# Sheet1.net
KiCad netlist of a schematic drawn in Altium Designer
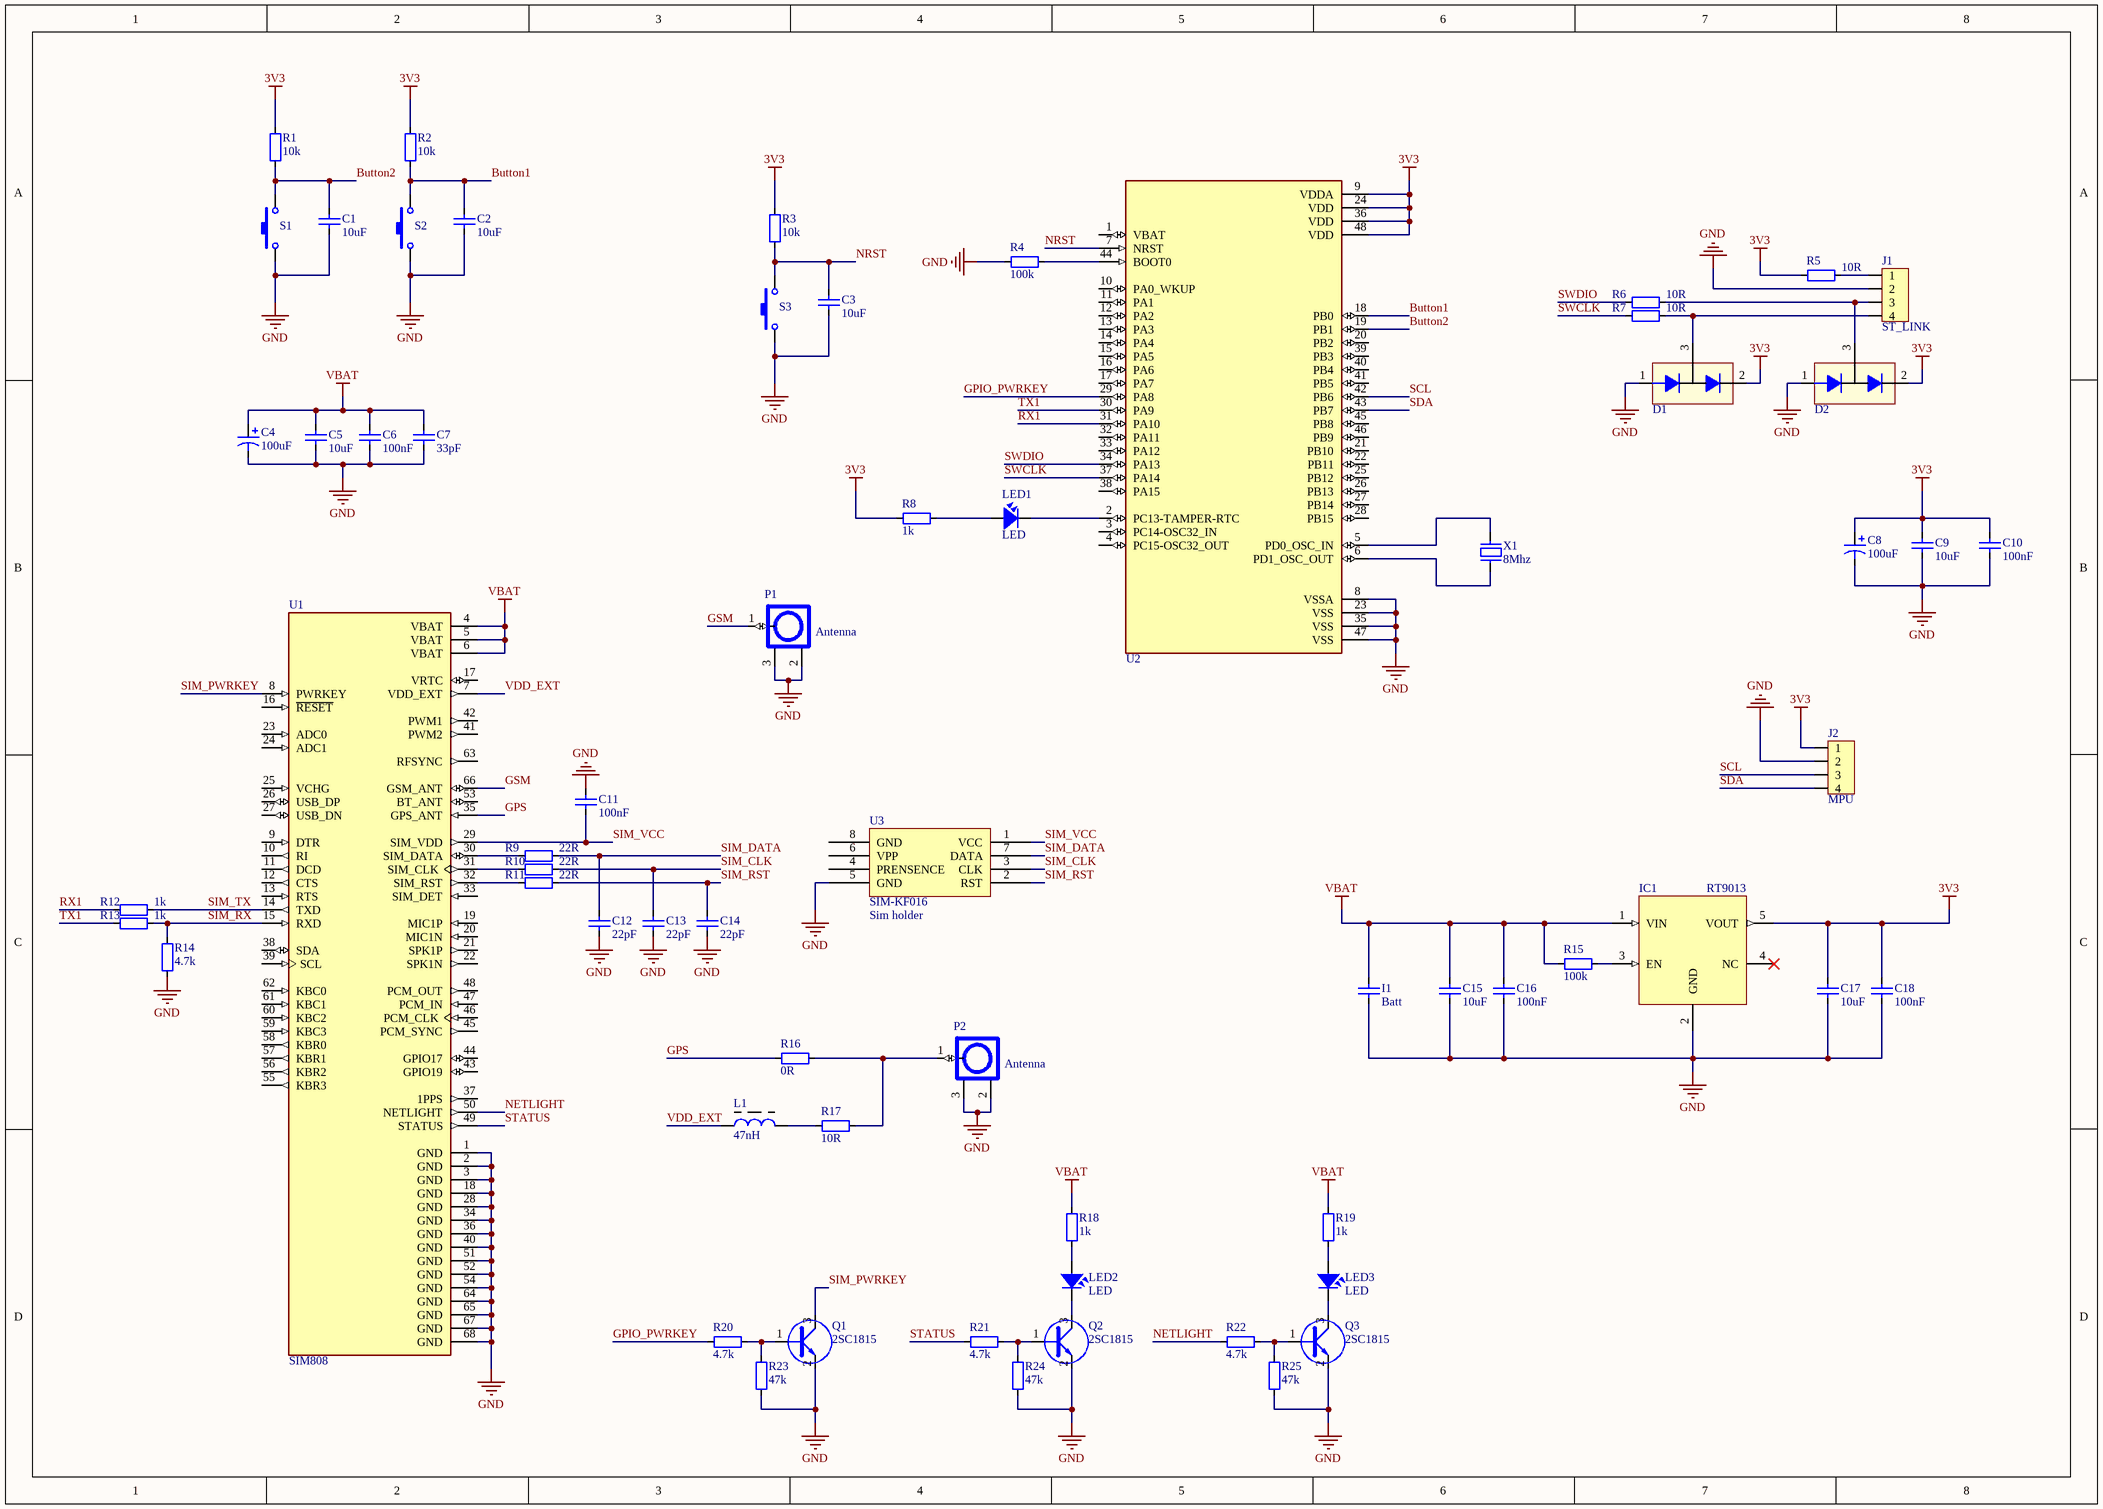
[diagram p0: Sheet1.SchDoc]

(export (version "E")
  (design (tool "Eeschema 10.0.6"))
  (components
    (comp (ref "C1")
      (value "10uF")
      (footprint "CAP_0603")
      (description "Capacitor")
      (fields (field (name "PUBLISHER") "Altium Limited"))
      (libsource (lib "My Library") (part "CapSMD"))
    )
    (comp (ref "C2")
      (value "10uF")
      (footprint "CAP_0603")
      (description "Capacitor")
      (fields (field (name "PUBLISHER") "Altium Limited"))
      (libsource (lib "My Library") (part "CapSMD"))
    )
    (comp (ref "C3")
      (value "10uF")
      (footprint "CAP_0603")
      (description "Capacitor")
      (fields (field (name "PUBLISHER") "Altium Limited"))
      (libsource (lib "My Library") (part "CapSMD"))
    )
    (comp (ref "C4")
      (value "100uF")
      (footprint "CAP_7343")
      (description "Tantalum")
      (fields (field (name "PUBLISHER") "Altium Limited"))
      (libsource (lib "My Library") (part "Cap Pol"))
    )
    (comp (ref "C5")
      (value "10uF")
      (footprint "CAP_0603")
      (description "Capacitor")
      (fields (field (name "PUBLISHER") "Altium Limited"))
      (libsource (lib "My Library") (part "CapSMD"))
    )
    (comp (ref "C6")
      (value "100nF")
      (footprint "CAP_0603")
      (description "Capacitor")
      (fields (field (name "PUBLISHER") "Altium Limited"))
      (libsource (lib "My Library") (part "CapSMD"))
    )
    (comp (ref "C7")
      (value "33pF")
      (footprint "CAP_0603")
      (description "Capacitor")
      (fields (field (name "PUBLISHER") "Altium Limited"))
      (libsource (lib "My Library") (part "CapSMD"))
    )
    (comp (ref "C8")
      (value "100uF")
      (footprint "CAP_7343")
      (description "Tantalum")
      (fields (field (name "PUBLISHER") "Altium Limited"))
      (libsource (lib "My Library") (part "Cap Pol"))
    )
    (comp (ref "C9")
      (value "10uF")
      (footprint "CAP_0603")
      (description "Capacitor")
      (fields (field (name "PUBLISHER") "Altium Limited"))
      (libsource (lib "My Library") (part "CapSMD"))
    )
    (comp (ref "C10")
      (value "100nF")
      (footprint "CAP_0603")
      (description "Capacitor")
      (fields (field (name "PUBLISHER") "Altium Limited"))
      (libsource (lib "My Library") (part "CapSMD"))
    )
    (comp (ref "C11")
      (value "100nF")
      (footprint "CAP_0603")
      (description "Capacitor")
      (fields (field (name "PUBLISHER") "Altium Limited"))
      (libsource (lib "My Library") (part "CapSMD"))
    )
    (comp (ref "C12")
      (value "22pF")
      (footprint "CAP_0603")
      (description "Capacitor")
      (fields (field (name "PUBLISHER") "Altium Limited"))
      (libsource (lib "My Library") (part "CapSMD"))
    )
    (comp (ref "C13")
      (value "22pF")
      (footprint "CAP_0603")
      (description "Capacitor")
      (fields (field (name "PUBLISHER") "Altium Limited"))
      (libsource (lib "My Library") (part "CapSMD"))
    )
    (comp (ref "C14")
      (value "22pF")
      (footprint "CAP_0603")
      (description "Capacitor")
      (fields (field (name "PUBLISHER") "Altium Limited"))
      (libsource (lib "My Library") (part "CapSMD"))
    )
    (comp (ref "C15")
      (value "10uF")
      (footprint "CAP_0603")
      (description "Capacitor")
      (fields (field (name "PUBLISHER") "Altium Limited"))
      (libsource (lib "My Library") (part "CapSMD"))
    )
    (comp (ref "C16")
      (value "100nF")
      (footprint "CAP_0603")
      (description "Capacitor")
      (fields (field (name "PUBLISHER") "Altium Limited"))
      (libsource (lib "My Library") (part "CapSMD"))
    )
    (comp (ref "C17")
      (value "10uF")
      (footprint "CAP_0603")
      (description "Capacitor")
      (fields (field (name "PUBLISHER") "Altium Limited"))
      (libsource (lib "My Library") (part "CapSMD"))
    )
    (comp (ref "C18")
      (value "100nF")
      (footprint "CAP_0603")
      (description "Capacitor")
      (fields (field (name "PUBLISHER") "Altium Limited"))
      (libsource (lib "My Library") (part "CapSMD"))
    )
    (comp (ref "D1")
      (value "DIODE-BAV99")
      (footprint "SOT23")
      (description "ZENER, SOT23,")
      (fields
        (field (name "MANUFACTURER") "ON Semiconductor / Fairchild")
        (field (name "MANUFACTURER PART NUMBER") "BAV99")
        (field (name ".CREATOR") "LeKhaLinh")
        (field (name ".CHECKPCB") "LeKhaLinh")
        (field (name ".CHECKSCH") "LeKhaLinh")
      )
      (libsource (lib "GPS_Traking_V1_1") (part "DIODE-BAV99"))
    )
    (comp (ref "D2")
      (value "DIODE-BAV99")
      (footprint "SOT23")
      (description "ZENER, SOT23,")
      (fields
        (field (name "MANUFACTURER") "ON Semiconductor / Fairchild")
        (field (name "MANUFACTURER PART NUMBER") "BAV99")
        (field (name ".CREATOR") "LeKhaLinh")
        (field (name ".CHECKPCB") "LeKhaLinh")
        (field (name ".CHECKSCH") "LeKhaLinh")
      )
      (libsource (lib "GPS_Traking_V1_1") (part "DIODE-BAV99"))
    )
    (comp (ref "I1")
      (value "Batt")
      (footprint "CAP_3216")
      (description "Pad")
      (fields (field (name "PUBLISHER") "Altium Limited"))
      (libsource (lib "My Library") (part "CapSMD"))
    )
    (comp (ref "IC1")
      (value "RT9013")
      (footprint "SOT23-5")
      (description "RT9013-33GB IC REG LINEAR 3.3V 500mA SOT23-5")
      (libsource (lib "My Library") (part "RT9013"))
    )
    (comp (ref "J1")
      (value "ST_LINK")
      (footprint "JP4-D1T")
      (description "Header IDC, 4 x 1 Pin Vertical 2.54mm Pitch (Non-Boxed, Male)")
      (fields
        (field (name "MANUFACTURER") "Würth Elektronik eiSos GmbH")
        (field (name "PARTNO") "613002143121")
        (field (name "CREATED BY") "Karrer Zheng")
      )
      (libsource (lib "My Library") (part "Header4"))
    )
    (comp (ref "J2")
      (value "MPU")
      (footprint "JP4-D1T")
      (description "Header IDC, 4 x 1 Pin Vertical 2.54mm Pitch (Non-Boxed, Male)")
      (fields
        (field (name "MANUFACTURER") "Würth Elektronik eiSos GmbH")
        (field (name "PARTNO") "613002143121")
        (field (name "CREATED BY") "Karrer Zheng")
      )
      (libsource (lib "My Library") (part "Header4"))
    )
    (comp (ref "L1")
      (value "47nH")
      (footprint "L-0805")
      (description "Inductor")
      (libsource (lib "My Library") (part "Inductor Ferit"))
    )
    (comp (ref "LED1")
      (value "LED")
      (footprint "LED-0805-Orange")
      (description "LED Single colour Green and Red")
      (libsource (lib "My Library") (part "LED"))
    )
    (comp (ref "LED2")
      (value "LED")
      (footprint "LED-0805-Yellow")
      (description "LED Single colour Green and Red")
      (libsource (lib "My Library") (part "LED"))
    )
    (comp (ref "LED3")
      (value "LED")
      (footprint "LED-0805-Red")
      (description "LED Single colour Green and Red")
      (libsource (lib "My Library") (part "LED"))
    )
    (comp (ref "P1")
      (value "Antenna")
      (footprint "IPXS")
      (description "Antenna GSM GPS")
      (libsource (lib "My Library") (part "IPXSx66"))
    )
    (comp (ref "P2")
      (value "Antenna")
      (footprint "IPXS")
      (description "Antenna GSM GPS")
      (libsource (lib "My Library") (part "IPXSx66"))
    )
    (comp (ref "Q1")
      (value "2SC1815")
      (footprint "SOT23D")
      (description "NPN 600mW, ECB")
      (libsource (lib "My Library") (part "2SC1815"))
    )
    (comp (ref "Q2")
      (value "2SC1815")
      (footprint "SOT23D")
      (description "NPN 600mW, ECB")
      (libsource (lib "My Library") (part "2SC1815"))
    )
    (comp (ref "Q3")
      (value "2SC1815")
      (footprint "SOT23D")
      (description "NPN 600mW, ECB")
      (libsource (lib "My Library") (part "2SC1815"))
    )
    (comp (ref "R1")
      (value "10k")
      (footprint "RES-SMD-0603")
      (description "Resistor")
      (fields
        (field (name "MANUFACTURER") "Generic Components")
        (field (name "PUBLISHER") "Altium Hobart Technology Centre")
      )
      (libsource (lib "My Library") (part "Resistor - SMD"))
    )
    (comp (ref "R2")
      (value "10k")
      (footprint "RES-SMD-0603")
      (description "Resistor")
      (fields
        (field (name "MANUFACTURER") "Generic Components")
        (field (name "PUBLISHER") "Altium Hobart Technology Centre")
      )
      (libsource (lib "My Library") (part "Resistor - SMD"))
    )
    (comp (ref "R3")
      (value "10k")
      (footprint "RES-SMD-0603")
      (description "Resistor")
      (fields
        (field (name "MANUFACTURER") "Generic Components")
        (field (name "PUBLISHER") "Altium Hobart Technology Centre")
      )
      (libsource (lib "My Library") (part "Resistor - SMD"))
    )
    (comp (ref "R4")
      (value "100k")
      (footprint "RES-SMD-0603")
      (description "Resistor")
      (fields
        (field (name "MANUFACTURER") "Generic Components")
        (field (name "PUBLISHER") "Altium Hobart Technology Centre")
      )
      (libsource (lib "My Library") (part "Resistor - SMD"))
    )
    (comp (ref "R5")
      (value "10R")
      (footprint "RES-SMD-0603")
      (description "Resistor")
      (fields
        (field (name "MANUFACTURER") "Generic Components")
        (field (name "PUBLISHER") "Altium Hobart Technology Centre")
      )
      (libsource (lib "My Library") (part "Resistor - SMD"))
    )
    (comp (ref "R6")
      (value "10R")
      (footprint "RES-SMD-0603")
      (description "Resistor")
      (fields
        (field (name "MANUFACTURER") "Generic Components")
        (field (name "PUBLISHER") "Altium Hobart Technology Centre")
      )
      (libsource (lib "My Library") (part "Resistor - SMD"))
    )
    (comp (ref "R7")
      (value "10R")
      (footprint "RES-SMD-0603")
      (description "Resistor")
      (fields
        (field (name "MANUFACTURER") "Generic Components")
        (field (name "PUBLISHER") "Altium Hobart Technology Centre")
      )
      (libsource (lib "My Library") (part "Resistor - SMD"))
    )
    (comp (ref "R8")
      (value "1k")
      (footprint "RES-SMD-0603")
      (description "Resistor")
      (fields
        (field (name "MANUFACTURER") "Generic Components")
        (field (name "PUBLISHER") "Altium Hobart Technology Centre")
      )
      (libsource (lib "My Library") (part "Resistor - SMD"))
    )
    (comp (ref "R9")
      (value "22R")
      (footprint "RES-SMD-0603")
      (description "Resistor")
      (fields
        (field (name "MANUFACTURER") "Generic Components")
        (field (name "PUBLISHER") "Altium Hobart Technology Centre")
      )
      (libsource (lib "My Library") (part "Resistor - SMD"))
    )
    (comp (ref "R10")
      (value "22R")
      (footprint "RES-SMD-0603")
      (description "Resistor")
      (fields
        (field (name "MANUFACTURER") "Generic Components")
        (field (name "PUBLISHER") "Altium Hobart Technology Centre")
      )
      (libsource (lib "My Library") (part "Resistor - SMD"))
    )
    (comp (ref "R11")
      (value "22R")
      (footprint "RES-SMD-0603")
      (description "Resistor")
      (fields
        (field (name "MANUFACTURER") "Generic Components")
        (field (name "PUBLISHER") "Altium Hobart Technology Centre")
      )
      (libsource (lib "My Library") (part "Resistor - SMD"))
    )
    (comp (ref "R12")
      (value "1k")
      (footprint "RES-SMD-0603")
      (description "Resistor")
      (fields
        (field (name "MANUFACTURER") "Generic Components")
        (field (name "PUBLISHER") "Altium Hobart Technology Centre")
      )
      (libsource (lib "My Library") (part "Resistor - SMD"))
    )
    (comp (ref "R13")
      (value "1k")
      (footprint "RES-SMD-0603")
      (description "Resistor")
      (fields
        (field (name "MANUFACTURER") "Generic Components")
        (field (name "PUBLISHER") "Altium Hobart Technology Centre")
      )
      (libsource (lib "My Library") (part "Resistor - SMD"))
    )
    (comp (ref "R14")
      (value "4.7k")
      (footprint "RES-SMD-0603")
      (description "Resistor")
      (fields
        (field (name "MANUFACTURER") "Generic Components")
        (field (name "PUBLISHER") "Altium Hobart Technology Centre")
      )
      (libsource (lib "My Library") (part "Resistor - SMD"))
    )
    (comp (ref "R15")
      (value "100k")
      (footprint "RES-SMD-0603")
      (description "Resistor")
      (fields
        (field (name "MANUFACTURER") "Generic Components")
        (field (name "PUBLISHER") "Altium Hobart Technology Centre")
      )
      (libsource (lib "My Library") (part "Resistor - SMD"))
    )
    (comp (ref "R16")
      (value "0R")
      (footprint "RES-SMD-0805")
      (description "Resistor")
      (fields
        (field (name "MANUFACTURER") "Generic Components")
        (field (name "PUBLISHER") "Altium Hobart Technology Centre")
      )
      (libsource (lib "My Library") (part "Resistor - SMD"))
    )
    (comp (ref "R17")
      (value "10R")
      (footprint "RES-SMD-0805")
      (description "Resistor")
      (fields
        (field (name "MANUFACTURER") "Generic Components")
        (field (name "PUBLISHER") "Altium Hobart Technology Centre")
      )
      (libsource (lib "My Library") (part "Resistor - SMD"))
    )
    (comp (ref "R18")
      (value "1k")
      (footprint "RES-SMD-0603")
      (description "Resistor")
      (fields
        (field (name "MANUFACTURER") "Generic Components")
        (field (name "PUBLISHER") "Altium Hobart Technology Centre")
      )
      (libsource (lib "My Library") (part "Resistor - SMD"))
    )
    (comp (ref "R19")
      (value "1k")
      (footprint "RES-SMD-0603")
      (description "Resistor")
      (fields
        (field (name "MANUFACTURER") "Generic Components")
        (field (name "PUBLISHER") "Altium Hobart Technology Centre")
      )
      (libsource (lib "My Library") (part "Resistor - SMD"))
    )
    (comp (ref "R20")
      (value "4.7k")
      (footprint "RES-SMD-0603")
      (description "Resistor")
      (fields
        (field (name "MANUFACTURER") "Generic Components")
        (field (name "PUBLISHER") "Altium Hobart Technology Centre")
      )
      (libsource (lib "My Library") (part "Resistor - SMD"))
    )
    (comp (ref "R21")
      (value "4.7k")
      (footprint "RES-SMD-0603")
      (description "Resistor")
      (fields
        (field (name "MANUFACTURER") "Generic Components")
        (field (name "PUBLISHER") "Altium Hobart Technology Centre")
      )
      (libsource (lib "My Library") (part "Resistor - SMD"))
    )
    (comp (ref "R22")
      (value "4.7k")
      (footprint "RES-SMD-0603")
      (description "Resistor")
      (fields
        (field (name "MANUFACTURER") "Generic Components")
        (field (name "PUBLISHER") "Altium Hobart Technology Centre")
      )
      (libsource (lib "My Library") (part "Resistor - SMD"))
    )
    (comp (ref "R23")
      (value "47k")
      (footprint "RES-SMD-0603")
      (description "Resistor")
      (fields
        (field (name "MANUFACTURER") "Generic Components")
        (field (name "PUBLISHER") "Altium Hobart Technology Centre")
      )
      (libsource (lib "My Library") (part "Resistor - SMD"))
    )
    (comp (ref "R24")
      (value "47k")
      (footprint "RES-SMD-0603")
      (description "Resistor")
      (fields
        (field (name "MANUFACTURER") "Generic Components")
        (field (name "PUBLISHER") "Altium Hobart Technology Centre")
      )
      (libsource (lib "My Library") (part "Resistor - SMD"))
    )
    (comp (ref "R25")
      (value "47k")
      (footprint "RES-SMD-0603")
      (description "Resistor")
      (fields
        (field (name "MANUFACTURER") "Generic Components")
        (field (name "PUBLISHER") "Altium Hobart Technology Centre")
      )
      (libsource (lib "My Library") (part "Resistor - SMD"))
    )
    (comp (ref "S1")
      (value "SW-SMD")
      (footprint "SW 3x2x4")
      (description "Switch")
      (fields (field (name "PUBLISHER") "Altium Limited"))
      (libsource (lib "My Library") (part "SW-SMD"))
    )
    (comp (ref "S2")
      (value "SW-SMD")
      (footprint "SW 3x2x4")
      (description "Switch")
      (fields (field (name "PUBLISHER") "Altium Limited"))
      (libsource (lib "My Library") (part "SW-SMD"))
    )
    (comp (ref "S3")
      (value "SW-SMD")
      (footprint "SW 3x2x4")
      (description "Switch")
      (fields (field (name "PUBLISHER") "Altium Limited"))
      (libsource (lib "My Library") (part "SW-SMD"))
    )
    (comp (ref "U1")
      (value "SIM808")
      (footprint "XCVR_SIM808")
      (description "SIM808 GPS, GPRS/GSM RF Arduino Platform Evaluation Expansion Board")
      (fields (field (name "MF") "Adafruit Industries"))
      (libsource (lib "My Library") (part "SIM808"))
    )
    (comp (ref "U2")
      (value "STM32")
      (footprint "LQFP 48")
      (description "STM32 ARM-based 32-bit MCU with 64 Kbytes Flash, 64-pin LQFP, Industrial Temperature")
      (libsource (lib "My Library") (part "STM32F103C8T6"))
    )
    (comp (ref "U3")
      (value "SIM-KF016")
      (footprint "Sim Socket")
      (description "SIM Card Holder KF-016")
      (fields (field (name "ALTIUM_VALUE") "Sim holder"))
      (libsource (lib "My Library") (part "Sim holder"))
    )
    (comp (ref "X1")
      (value "8Mhz")
      (footprint "XTAL 5032 SMD")
      (description "Crystal For all Crystal 2pin.")
      (libsource (lib "My Library") (part "XT2"))
    )
  )
  (nets
    (net (code "1") (name "/Button1") (class "Default")
      (node (ref "C2") (pin "2") (pinfunction "2_2") (pintype "passive"))
      (node (ref "R2") (pin "1") (pinfunction "1_1") (pintype "passive"))
      (node (ref "S2") (pin "2") (pinfunction "2_2") (pintype "passive"))
      (node (ref "U2") (pin "18") (pinfunction "PB0_18") (pintype "bidirectional"))
    )
    (net (code "2") (name "/Button2") (class "Default")
      (node (ref "C1") (pin "2") (pinfunction "2_2") (pintype "passive"))
      (node (ref "R1") (pin "1") (pinfunction "1_1") (pintype "passive"))
      (node (ref "S1") (pin "2") (pinfunction "2_2") (pintype "passive"))
      (node (ref "U2") (pin "19") (pinfunction "PB1_19") (pintype "bidirectional"))
    )
    (net (code "3") (name "/GPIO_PWRKEY") (class "Default")
      (node (ref "R20") (pin "1") (pinfunction "1_1") (pintype "passive"))
      (node (ref "U2") (pin "29") (pinfunction "PA8_29") (pintype "bidirectional"))
    )
    (net (code "4") (name "/GPS") (class "Default")
      (node (ref "R16") (pin "1") (pinfunction "1_1") (pintype "passive"))
      (node (ref "U1") (pin "35") (pinfunction "GPS_ANT_35") (pintype "input"))
    )
    (net (code "5") (name "/GSM") (class "Default")
      (node (ref "P1") (pin "1") (pintype "bidirectional"))
      (node (ref "U1") (pin "66") (pinfunction "GSM_ANT_66") (pintype "bidirectional"))
    )
    (net (code "6") (name "/NETLIGHT") (class "Default")
      (node (ref "R22") (pin "1") (pinfunction "1_1") (pintype "passive"))
      (node (ref "U1") (pin "50") (pinfunction "NETLIGHT_50") (pintype "output"))
    )
    (net (code "7") (name "/NRST") (class "Default")
      (node (ref "C3") (pin "2") (pinfunction "2_2") (pintype "passive"))
      (node (ref "R3") (pin "1") (pinfunction "1_1") (pintype "passive"))
      (node (ref "S3") (pin "2") (pinfunction "2_2") (pintype "passive"))
      (node (ref "U2") (pin "7") (pinfunction "NRST_7") (pintype "input"))
    )
    (net (code "8") (name "/RX1") (class "Default")
      (node (ref "R12") (pin "2") (pinfunction "2_2") (pintype "passive"))
      (node (ref "U2") (pin "31") (pinfunction "PA10_31") (pintype "bidirectional"))
    )
    (net (code "9") (name "/SCL") (class "Default")
      (node (ref "J2") (pin "3") (pinfunction "3_3") (pintype "passive"))
      (node (ref "U2") (pin "42") (pinfunction "PB6_42") (pintype "bidirectional"))
    )
    (net (code "10") (name "/SDA") (class "Default")
      (node (ref "J2") (pin "4") (pinfunction "4_4") (pintype "passive"))
      (node (ref "U2") (pin "43") (pinfunction "PB7_43") (pintype "bidirectional"))
    )
    (net (code "11") (name "/SIM_CLK") (class "Default")
      (node (ref "C13") (pin "1") (pinfunction "1_1") (pintype "passive"))
      (node (ref "R10") (pin "1") (pinfunction "1_1") (pintype "passive"))
      (node (ref "U3") (pin "3") (pinfunction "CLK_3") (pintype "passive"))
    )
    (net (code "12") (name "/SIM_DATA") (class "Default")
      (node (ref "C12") (pin "1") (pinfunction "1_1") (pintype "passive"))
      (node (ref "R9") (pin "1") (pinfunction "1_1") (pintype "passive"))
      (node (ref "U3") (pin "7") (pinfunction "DATA_7") (pintype "passive"))
    )
    (net (code "13") (name "/SIM_PWRKEY") (class "Default")
      (node (ref "Q1") (pin "3") (pinfunction "C_3") (pintype "passive"))
      (node (ref "U1") (pin "8") (pinfunction "PWRKEY_8") (pintype "input"))
    )
    (net (code "14") (name "/SIM_RST") (class "Default")
      (node (ref "C14") (pin "1") (pinfunction "1_1") (pintype "passive"))
      (node (ref "R11") (pin "1") (pinfunction "1_1") (pintype "passive"))
      (node (ref "U3") (pin "2") (pinfunction "RST_2") (pintype "passive"))
    )
    (net (code "15") (name "/SIM_RX") (class "Default")
      (node (ref "R13") (pin "1") (pinfunction "1_1") (pintype "passive"))
      (node (ref "R14") (pin "1") (pinfunction "1_1") (pintype "passive"))
      (node (ref "U1") (pin "15") (pinfunction "RXD_15") (pintype "input"))
    )
    (net (code "16") (name "/SIM_TX") (class "Default")
      (node (ref "R12") (pin "1") (pinfunction "1_1") (pintype "passive"))
      (node (ref "U1") (pin "14") (pinfunction "TXD_14") (pintype "output"))
    )
    (net (code "17") (name "/SIM_VCC") (class "Default")
      (node (ref "C11") (pin "2") (pinfunction "2_2") (pintype "passive"))
      (node (ref "U1") (pin "29") (pinfunction "SIM_VDD_29") (pintype "output"))
      (node (ref "U3") (pin "1") (pinfunction "VCC_1") (pintype "passive"))
    )
    (net (code "18") (name "/STATUS") (class "Default")
      (node (ref "R21") (pin "1") (pinfunction "1_1") (pintype "passive"))
      (node (ref "U1") (pin "49") (pinfunction "STATUS_49") (pintype "output"))
    )
    (net (code "19") (name "/SWCLK") (class "Default")
      (node (ref "R7") (pin "1") (pinfunction "1_1") (pintype "passive"))
      (node (ref "U2") (pin "37") (pinfunction "PA14_37") (pintype "bidirectional"))
    )
    (net (code "20") (name "/SWDIO") (class "Default")
      (node (ref "R6") (pin "1") (pinfunction "1_1") (pintype "passive"))
      (node (ref "U2") (pin "34") (pinfunction "PA13_34") (pintype "bidirectional"))
    )
    (net (code "21") (name "/TX1") (class "Default")
      (node (ref "R13") (pin "2") (pinfunction "2_2") (pintype "passive"))
      (node (ref "U2") (pin "30") (pinfunction "PA9_30") (pintype "bidirectional"))
    )
    (net (code "22") (name "/VDD_EXT") (class "Default")
      (node (ref "L1") (pin "1") (pinfunction "1_1") (pintype "passive"))
      (node (ref "U1") (pin "7") (pinfunction "VDD_EXT_7") (pintype "output"))
    )
    (net (code "23") (name "3V3") (class "Default")
      (node (ref "C10") (pin "2") (pinfunction "2_2") (pintype "passive"))
      (node (ref "C17") (pin "2") (pinfunction "2_2") (pintype "passive"))
      (node (ref "C18") (pin "2") (pinfunction "2_2") (pintype "passive"))
      (node (ref "C8") (pin "1") (pinfunction "1_1") (pintype "passive"))
      (node (ref "C9") (pin "2") (pinfunction "2_2") (pintype "passive"))
      (node (ref "D1") (pin "2") (pinfunction "2_2") (pintype "passive"))
      (node (ref "D2") (pin "2") (pinfunction "2_2") (pintype "passive"))
      (node (ref "IC1") (pin "5") (pinfunction "VOUT_5") (pintype "output"))
      (node (ref "J2") (pin "1") (pinfunction "1_1") (pintype "passive"))
      (node (ref "R1") (pin "2") (pinfunction "2_2") (pintype "passive"))
      (node (ref "R2") (pin "2") (pinfunction "2_2") (pintype "passive"))
      (node (ref "R3") (pin "2") (pinfunction "2_2") (pintype "passive"))
      (node (ref "R5") (pin "1") (pinfunction "1_1") (pintype "passive"))
      (node (ref "R8") (pin "1") (pinfunction "1_1") (pintype "passive"))
      (node (ref "U2") (pin "24") (pinfunction "VDD_24") (pintype "power_in"))
      (node (ref "U2") (pin "36") (pinfunction "VDD_36") (pintype "power_in"))
      (node (ref "U2") (pin "48") (pinfunction "VDD_48") (pintype "power_in"))
      (node (ref "U2") (pin "9") (pinfunction "VDDA_9") (pintype "power_in"))
    )
    (net (code "24") (name "GND") (class "Default")
      (node (ref "C1") (pin "1") (pinfunction "1_1") (pintype "passive"))
      (node (ref "C10") (pin "1") (pinfunction "1_1") (pintype "passive"))
      (node (ref "C11") (pin "1") (pinfunction "1_1") (pintype "passive"))
      (node (ref "C12") (pin "2") (pinfunction "2_2") (pintype "passive"))
      (node (ref "C13") (pin "2") (pinfunction "2_2") (pintype "passive"))
      (node (ref "C14") (pin "2") (pinfunction "2_2") (pintype "passive"))
      (node (ref "C15") (pin "1") (pinfunction "1_1") (pintype "passive"))
      (node (ref "C16") (pin "1") (pinfunction "1_1") (pintype "passive"))
      (node (ref "C17") (pin "1") (pinfunction "1_1") (pintype "passive"))
      (node (ref "C18") (pin "1") (pinfunction "1_1") (pintype "passive"))
      (node (ref "C2") (pin "1") (pinfunction "1_1") (pintype "passive"))
      (node (ref "C3") (pin "1") (pinfunction "1_1") (pintype "passive"))
      (node (ref "C4") (pin "2") (pinfunction "2_2") (pintype "passive"))
      (node (ref "C5") (pin "1") (pinfunction "1_1") (pintype "passive"))
      (node (ref "C6") (pin "1") (pinfunction "1_1") (pintype "passive"))
      (node (ref "C7") (pin "1") (pinfunction "1_1") (pintype "passive"))
      (node (ref "C8") (pin "2") (pinfunction "2_2") (pintype "passive"))
      (node (ref "C9") (pin "1") (pinfunction "1_1") (pintype "passive"))
      (node (ref "D1") (pin "1") (pinfunction "1_1") (pintype "passive"))
      (node (ref "D2") (pin "1") (pinfunction "1_1") (pintype "passive"))
      (node (ref "I1") (pin "1") (pinfunction "1_1") (pintype "passive"))
      (node (ref "IC1") (pin "2") (pinfunction "GND_2") (pintype "passive"))
      (node (ref "J1") (pin "2") (pinfunction "2_2") (pintype "passive"))
      (node (ref "J2") (pin "2") (pinfunction "2_2") (pintype "passive"))
      (node (ref "P1") (pin "2") (pintype "passive"))
      (node (ref "P1") (pin "3") (pintype "passive"))
      (node (ref "P2") (pin "2") (pintype "passive"))
      (node (ref "P2") (pin "3") (pintype "passive"))
      (node (ref "Q1") (pin "2") (pinfunction "E_2") (pintype "passive"))
      (node (ref "Q2") (pin "2") (pinfunction "E_2") (pintype "passive"))
      (node (ref "Q3") (pin "2") (pinfunction "E_2") (pintype "passive"))
      (node (ref "R14") (pin "2") (pinfunction "2_2") (pintype "passive"))
      (node (ref "R23") (pin "1") (pinfunction "1_1") (pintype "passive"))
      (node (ref "R24") (pin "1") (pinfunction "1_1") (pintype "passive"))
      (node (ref "R25") (pin "1") (pinfunction "1_1") (pintype "passive"))
      (node (ref "R4") (pin "2") (pinfunction "2_2") (pintype "passive"))
      (node (ref "S1") (pin "1") (pinfunction "1_1") (pintype "passive"))
      (node (ref "S2") (pin "1") (pinfunction "1_1") (pintype "passive"))
      (node (ref "S3") (pin "1") (pinfunction "1_1") (pintype "passive"))
      (node (ref "U1") (pin "1") (pinfunction "GND_1") (pintype "power_in"))
      (node (ref "U1") (pin "18") (pinfunction "GND_18") (pintype "power_in"))
      (node (ref "U1") (pin "2") (pinfunction "GND_2") (pintype "power_in"))
      (node (ref "U1") (pin "28") (pinfunction "GND_28") (pintype "power_in"))
      (node (ref "U1") (pin "3") (pinfunction "GND_3") (pintype "power_in"))
      (node (ref "U1") (pin "34") (pinfunction "GND_34") (pintype "power_in"))
      (node (ref "U1") (pin "36") (pinfunction "GND_36") (pintype "power_in"))
      (node (ref "U1") (pin "40") (pinfunction "GND_40") (pintype "power_in"))
      (node (ref "U1") (pin "51") (pinfunction "GND_51") (pintype "power_in"))
      (node (ref "U1") (pin "52") (pinfunction "GND_52") (pintype "power_in"))
      (node (ref "U1") (pin "54") (pinfunction "GND_54") (pintype "power_in"))
      (node (ref "U1") (pin "64") (pinfunction "GND_64") (pintype "power_in"))
      (node (ref "U1") (pin "65") (pinfunction "GND_65") (pintype "power_in"))
      (node (ref "U1") (pin "67") (pinfunction "GND_67") (pintype "power_in"))
      (node (ref "U1") (pin "68") (pinfunction "GND_68") (pintype "power_in"))
      (node (ref "U2") (pin "23") (pinfunction "VSS_23") (pintype "power_in"))
      (node (ref "U2") (pin "35") (pinfunction "VSS_35") (pintype "power_in"))
      (node (ref "U2") (pin "47") (pinfunction "VSS_47") (pintype "power_in"))
      (node (ref "U2") (pin "8") (pinfunction "VSSA_8") (pintype "power_in"))
      (node (ref "U3") (pin "5") (pinfunction "GND_5") (pintype "passive"))
    )
    (net (code "25") (name "Net-(D1-Pad3)") (class "Default")
      (node (ref "D1") (pin "3") (pinfunction "3_3") (pintype "passive"))
      (node (ref "J1") (pin "4") (pinfunction "4_4") (pintype "passive"))
      (node (ref "R7") (pin "2") (pinfunction "2_2") (pintype "passive"))
    )
    (net (code "26") (name "Net-(D2-Pad3)") (class "Default")
      (node (ref "D2") (pin "3") (pinfunction "3_3") (pintype "passive"))
      (node (ref "J1") (pin "3") (pinfunction "3_3") (pintype "passive"))
      (node (ref "R6") (pin "2") (pinfunction "2_2") (pintype "passive"))
    )
    (net (code "27") (name "Net-(IC1-EN)") (class "Default")
      (node (ref "IC1") (pin "3") (pinfunction "EN_3") (pintype "input"))
      (node (ref "R15") (pin "1") (pinfunction "1_1") (pintype "passive"))
    )
    (net (code "28") (name "Net-(J1-Pad1)") (class "Default")
      (node (ref "J1") (pin "1") (pinfunction "1_1") (pintype "passive"))
      (node (ref "R5") (pin "2") (pinfunction "2_2") (pintype "passive"))
    )
    (net (code "29") (name "Net-(L1-Pad2)") (class "Default")
      (node (ref "L1") (pin "2") (pinfunction "2_2") (pintype "passive"))
      (node (ref "R17") (pin "2") (pinfunction "2_2") (pintype "passive"))
    )
    (net (code "30") (name "Net-(LED1-Pad1)") (class "Default")
      (node (ref "LED1") (pin "1") (pinfunction "1_1") (pintype "passive"))
      (node (ref "R8") (pin "2") (pinfunction "2_2") (pintype "passive"))
    )
    (net (code "31") (name "Net-(LED2-Pad1)") (class "Default")
      (node (ref "LED2") (pin "1") (pinfunction "1_1") (pintype "passive"))
      (node (ref "R18") (pin "1") (pinfunction "1_1") (pintype "passive"))
    )
    (net (code "32") (name "Net-(LED3-Pad1)") (class "Default")
      (node (ref "LED3") (pin "1") (pinfunction "1_1") (pintype "passive"))
      (node (ref "R19") (pin "1") (pinfunction "1_1") (pintype "passive"))
    )
    (net (code "33") (name "Net-(P2-Pad1)") (class "Default")
      (node (ref "P2") (pin "1") (pintype "bidirectional"))
      (node (ref "R16") (pin "2") (pinfunction "2_2") (pintype "passive"))
      (node (ref "R17") (pin "1") (pinfunction "1_1") (pintype "passive"))
    )
    (net (code "34") (name "Net-(Q1-B)") (class "Default")
      (node (ref "Q1") (pin "1") (pinfunction "B_1") (pintype "passive"))
      (node (ref "R20") (pin "2") (pinfunction "2_2") (pintype "passive"))
      (node (ref "R23") (pin "2") (pinfunction "2_2") (pintype "passive"))
    )
    (net (code "35") (name "Net-(Q2-B)") (class "Default")
      (node (ref "Q2") (pin "1") (pinfunction "B_1") (pintype "passive"))
      (node (ref "R21") (pin "2") (pinfunction "2_2") (pintype "passive"))
      (node (ref "R24") (pin "2") (pinfunction "2_2") (pintype "passive"))
    )
    (net (code "36") (name "Net-(Q2-C)") (class "Default")
      (node (ref "LED2") (pin "2") (pinfunction "2_2") (pintype "passive"))
      (node (ref "Q2") (pin "3") (pinfunction "C_3") (pintype "passive"))
    )
    (net (code "37") (name "Net-(Q3-B)") (class "Default")
      (node (ref "Q3") (pin "1") (pinfunction "B_1") (pintype "passive"))
      (node (ref "R22") (pin "2") (pinfunction "2_2") (pintype "passive"))
      (node (ref "R25") (pin "2") (pinfunction "2_2") (pintype "passive"))
    )
    (net (code "38") (name "Net-(Q3-C)") (class "Default")
      (node (ref "LED3") (pin "2") (pinfunction "2_2") (pintype "passive"))
      (node (ref "Q3") (pin "3") (pinfunction "C_3") (pintype "passive"))
    )
    (net (code "39") (name "Net-(U1-SIM_CLK)") (class "Default")
      (node (ref "R10") (pin "2") (pinfunction "2_2") (pintype "passive"))
      (node (ref "U1") (pin "31") (pinfunction "SIM_CLK_31") (pintype "output"))
    )
    (net (code "40") (name "Net-(U1-SIM_DATA)") (class "Default")
      (node (ref "R9") (pin "2") (pinfunction "2_2") (pintype "passive"))
      (node (ref "U1") (pin "30") (pinfunction "SIM_DATA_30") (pintype "bidirectional"))
    )
    (net (code "41") (name "Net-(U1-SIM_RST)") (class "Default")
      (node (ref "R11") (pin "2") (pinfunction "2_2") (pintype "passive"))
      (node (ref "U1") (pin "32") (pinfunction "SIM_RST_32") (pintype "output"))
    )
    (net (code "42") (name "Net-(U2-BOOT0)") (class "Default")
      (node (ref "R4") (pin "1") (pinfunction "1_1") (pintype "passive"))
      (node (ref "U2") (pin "44") (pinfunction "BOOT0_44") (pintype "input"))
    )
    (net (code "43") (name "Net-(U2-PC13-TAMPER-RTC)") (class "Default")
      (node (ref "LED1") (pin "2") (pinfunction "2_2") (pintype "passive"))
      (node (ref "U2") (pin "2") (pinfunction "PC13-TAMPER-RTC_2") (pintype "bidirectional"))
    )
    (net (code "44") (name "Net-(U2-PD0_OSC_IN)") (class "Default")
      (node (ref "U2") (pin "5") (pinfunction "PD0_OSC_IN_5") (pintype "bidirectional"))
      (node (ref "X1") (pin "2") (pinfunction "2_2") (pintype "passive"))
    )
    (net (code "45") (name "Net-(U2-PD1_OSC_OUT)") (class "Default")
      (node (ref "U2") (pin "6") (pinfunction "PD1_OSC_OUT_6") (pintype "bidirectional"))
      (node (ref "X1") (pin "1") (pinfunction "1_1") (pintype "passive"))
    )
    (net (code "46") (name "VBAT") (class "Default")
      (node (ref "C15") (pin "2") (pinfunction "2_2") (pintype "passive"))
      (node (ref "C16") (pin "2") (pinfunction "2_2") (pintype "passive"))
      (node (ref "C4") (pin "1") (pinfunction "1_1") (pintype "passive"))
      (node (ref "C5") (pin "2") (pinfunction "2_2") (pintype "passive"))
      (node (ref "C6") (pin "2") (pinfunction "2_2") (pintype "passive"))
      (node (ref "C7") (pin "2") (pinfunction "2_2") (pintype "passive"))
      (node (ref "I1") (pin "2") (pinfunction "2_2") (pintype "passive"))
      (node (ref "IC1") (pin "1") (pinfunction "VIN_1") (pintype "input"))
      (node (ref "R15") (pin "2") (pinfunction "2_2") (pintype "passive"))
      (node (ref "R18") (pin "2") (pinfunction "2_2") (pintype "passive"))
      (node (ref "R19") (pin "2") (pinfunction "2_2") (pintype "passive"))
      (node (ref "U1") (pin "4") (pinfunction "VBAT_4") (pintype "power_in"))
      (node (ref "U1") (pin "5") (pinfunction "VBAT_5") (pintype "power_in"))
      (node (ref "U1") (pin "6") (pinfunction "VBAT_6") (pintype "power_in"))
    )
    (net (code "47") (name "unconnected-(IC1-NC-Pad4)") (class "Default")
      (node (ref "IC1") (pin "4") (pinfunction "NC_4") (pintype "passive+no_connect"))
    )
    (net (code "48") (name "unconnected-(U1-1PPS-Pad37)") (class "Default")
      (node (ref "U1") (pin "37") (pinfunction "1PPS_37") (pintype "output"))
    )
    (net (code "49") (name "unconnected-(U1-ADC0-Pad23)") (class "Default")
      (node (ref "U1") (pin "23") (pinfunction "ADC0_23") (pintype "input"))
    )
    (net (code "50") (name "unconnected-(U1-ADC1-Pad24)") (class "Default")
      (node (ref "U1") (pin "24") (pinfunction "ADC1_24") (pintype "input"))
    )
    (net (code "51") (name "unconnected-(U1-BT_ANT-Pad53)") (class "Default")
      (node (ref "U1") (pin "53") (pinfunction "BT_ANT_53") (pintype "bidirectional"))
    )
    (net (code "52") (name "unconnected-(U1-CTS-Pad12)") (class "Default")
      (node (ref "U1") (pin "12") (pinfunction "CTS_12") (pintype "output"))
    )
    (net (code "53") (name "unconnected-(U1-DCD-Pad11)") (class "Default")
      (node (ref "U1") (pin "11") (pinfunction "DCD_11") (pintype "output"))
    )
    (net (code "54") (name "unconnected-(U1-DTR-Pad9)") (class "Default")
      (node (ref "U1") (pin "9") (pinfunction "DTR_9") (pintype "input"))
    )
    (net (code "55") (name "unconnected-(U1-GPIO17-Pad44)") (class "Default")
      (node (ref "U1") (pin "44") (pinfunction "GPIO17_44") (pintype "bidirectional"))
    )
    (net (code "56") (name "unconnected-(U1-GPIO19-Pad43)") (class "Default")
      (node (ref "U1") (pin "43") (pinfunction "GPIO19_43") (pintype "bidirectional"))
    )
    (net (code "57") (name "unconnected-(U1-KBC0-Pad62)") (class "Default")
      (node (ref "U1") (pin "62") (pinfunction "KBC0_62") (pintype "input"))
    )
    (net (code "58") (name "unconnected-(U1-KBC1-Pad61)") (class "Default")
      (node (ref "U1") (pin "61") (pinfunction "KBC1_61") (pintype "input"))
    )
    (net (code "59") (name "unconnected-(U1-KBC2-Pad60)") (class "Default")
      (node (ref "U1") (pin "60") (pinfunction "KBC2_60") (pintype "input"))
    )
    (net (code "60") (name "unconnected-(U1-KBC3-Pad59)") (class "Default")
      (node (ref "U1") (pin "59") (pinfunction "KBC3_59") (pintype "input"))
    )
    (net (code "61") (name "unconnected-(U1-KBR0-Pad58)") (class "Default")
      (node (ref "U1") (pin "58") (pinfunction "KBR0_58") (pintype "output"))
    )
    (net (code "62") (name "unconnected-(U1-KBR1-Pad57)") (class "Default")
      (node (ref "U1") (pin "57") (pinfunction "KBR1_57") (pintype "output"))
    )
    (net (code "63") (name "unconnected-(U1-KBR2-Pad56)") (class "Default")
      (node (ref "U1") (pin "56") (pinfunction "KBR2_56") (pintype "output"))
    )
    (net (code "64") (name "unconnected-(U1-KBR3-Pad55)") (class "Default")
      (node (ref "U1") (pin "55") (pinfunction "KBR3_55") (pintype "output"))
    )
    (net (code "65") (name "unconnected-(U1-MIC1N-Pad20)") (class "Default")
      (node (ref "U1") (pin "20") (pinfunction "MIC1N_20") (pintype "input"))
    )
    (net (code "66") (name "unconnected-(U1-MIC1P-Pad19)") (class "Default")
      (node (ref "U1") (pin "19") (pinfunction "MIC1P_19") (pintype "input"))
    )
    (net (code "67") (name "unconnected-(U1-PCM_CLK-Pad46)") (class "Default")
      (node (ref "U1") (pin "46") (pinfunction "PCM_CLK_46") (pintype "input"))
    )
    (net (code "68") (name "unconnected-(U1-PCM_IN-Pad47)") (class "Default")
      (node (ref "U1") (pin "47") (pinfunction "PCM_IN_47") (pintype "input"))
    )
    (net (code "69") (name "unconnected-(U1-PCM_OUT-Pad48)") (class "Default")
      (node (ref "U1") (pin "48") (pinfunction "PCM_OUT_48") (pintype "output"))
    )
    (net (code "70") (name "unconnected-(U1-PCM_SYNC-Pad45)") (class "Default")
      (node (ref "U1") (pin "45") (pinfunction "PCM_SYNC_45") (pintype "output"))
    )
    (net (code "71") (name "unconnected-(U1-PWM1-Pad42)") (class "Default")
      (node (ref "U1") (pin "42") (pinfunction "PWM1_42") (pintype "output"))
    )
    (net (code "72") (name "unconnected-(U1-PWM2-Pad41)") (class "Default")
      (node (ref "U1") (pin "41") (pinfunction "PWM2_41") (pintype "output"))
    )
    (net (code "73") (name "unconnected-(U1-RFSYNC-Pad63)") (class "Default")
      (node (ref "U1") (pin "63") (pinfunction "RFSYNC_63") (pintype "output"))
    )
    (net (code "74") (name "unconnected-(U1-RI-Pad10)") (class "Default")
      (node (ref "U1") (pin "10") (pinfunction "RI_10") (pintype "output"))
    )
    (net (code "75") (name "unconnected-(U1-RTS-Pad13)") (class "Default")
      (node (ref "U1") (pin "13") (pinfunction "RTS_13") (pintype "input"))
    )
    (net (code "76") (name "unconnected-(U1-SCL-Pad39)") (class "Default")
      (node (ref "U1") (pin "39") (pinfunction "SCL_39") (pintype "input"))
    )
    (net (code "77") (name "unconnected-(U1-SDA-Pad38)") (class "Default")
      (node (ref "U1") (pin "38") (pinfunction "SDA_38") (pintype "bidirectional"))
    )
    (net (code "78") (name "unconnected-(U1-SIM_DET-Pad33)") (class "Default")
      (node (ref "U1") (pin "33") (pinfunction "SIM_DET_33") (pintype "input"))
    )
    (net (code "79") (name "unconnected-(U1-SPK1N-Pad22)") (class "Default")
      (node (ref "U1") (pin "22") (pinfunction "SPK1N_22") (pintype "output"))
    )
    (net (code "80") (name "unconnected-(U1-SPK1P-Pad21)") (class "Default")
      (node (ref "U1") (pin "21") (pinfunction "SPK1P_21") (pintype "output"))
    )
    (net (code "81") (name "unconnected-(U1-USB_DN-Pad27)") (class "Default")
      (node (ref "U1") (pin "27") (pinfunction "USB_DN_27") (pintype "bidirectional"))
    )
    (net (code "82") (name "unconnected-(U1-USB_DP-Pad26)") (class "Default")
      (node (ref "U1") (pin "26") (pinfunction "USB_DP_26") (pintype "bidirectional"))
    )
    (net (code "83") (name "unconnected-(U1-VCHG-Pad25)") (class "Default")
      (node (ref "U1") (pin "25") (pinfunction "VCHG_25") (pintype "input"))
    )
    (net (code "84") (name "unconnected-(U1-VRTC-Pad17)") (class "Default")
      (node (ref "U1") (pin "17") (pinfunction "VRTC_17") (pintype "bidirectional"))
    )
    (net (code "85") (name "unconnected-(U1-~{RESET}-Pad16)") (class "Default")
      (node (ref "U1") (pin "16") (pinfunction "~{RESET}_16") (pintype "input"))
    )
    (net (code "86") (name "unconnected-(U2-PA0_WKUP-Pad10)") (class "Default")
      (node (ref "U2") (pin "10") (pinfunction "PA0_WKUP_10") (pintype "bidirectional"))
    )
    (net (code "87") (name "unconnected-(U2-PA1-Pad11)") (class "Default")
      (node (ref "U2") (pin "11") (pinfunction "PA1_11") (pintype "bidirectional"))
    )
    (net (code "88") (name "unconnected-(U2-PA2-Pad12)") (class "Default")
      (node (ref "U2") (pin "12") (pinfunction "PA2_12") (pintype "bidirectional"))
    )
    (net (code "89") (name "unconnected-(U2-PA3-Pad13)") (class "Default")
      (node (ref "U2") (pin "13") (pinfunction "PA3_13") (pintype "bidirectional"))
    )
    (net (code "90") (name "unconnected-(U2-PA4-Pad14)") (class "Default")
      (node (ref "U2") (pin "14") (pinfunction "PA4_14") (pintype "bidirectional"))
    )
    (net (code "91") (name "unconnected-(U2-PA5-Pad15)") (class "Default")
      (node (ref "U2") (pin "15") (pinfunction "PA5_15") (pintype "bidirectional"))
    )
    (net (code "92") (name "unconnected-(U2-PA6-Pad16)") (class "Default")
      (node (ref "U2") (pin "16") (pinfunction "PA6_16") (pintype "bidirectional"))
    )
    (net (code "93") (name "unconnected-(U2-PA7-Pad17)") (class "Default")
      (node (ref "U2") (pin "17") (pinfunction "PA7_17") (pintype "bidirectional"))
    )
    (net (code "94") (name "unconnected-(U2-PA11-Pad32)") (class "Default")
      (node (ref "U2") (pin "32") (pinfunction "PA11_32") (pintype "bidirectional"))
    )
    (net (code "95") (name "unconnected-(U2-PA12-Pad33)") (class "Default")
      (node (ref "U2") (pin "33") (pinfunction "PA12_33") (pintype "bidirectional"))
    )
    (net (code "96") (name "unconnected-(U2-PA15-Pad38)") (class "Default")
      (node (ref "U2") (pin "38") (pinfunction "PA15_38") (pintype "bidirectional"))
    )
    (net (code "97") (name "unconnected-(U2-PB2-Pad20)") (class "Default")
      (node (ref "U2") (pin "20") (pinfunction "PB2_20") (pintype "bidirectional"))
    )
    (net (code "98") (name "unconnected-(U2-PB3-Pad39)") (class "Default")
      (node (ref "U2") (pin "39") (pinfunction "PB3_39") (pintype "bidirectional"))
    )
    (net (code "99") (name "unconnected-(U2-PB4-Pad40)") (class "Default")
      (node (ref "U2") (pin "40") (pinfunction "PB4_40") (pintype "bidirectional"))
    )
    (net (code "100") (name "unconnected-(U2-PB5-Pad41)") (class "Default")
      (node (ref "U2") (pin "41") (pinfunction "PB5_41") (pintype "bidirectional"))
    )
    (net (code "101") (name "unconnected-(U2-PB8-Pad45)") (class "Default")
      (node (ref "U2") (pin "45") (pinfunction "PB8_45") (pintype "bidirectional"))
    )
    (net (code "102") (name "unconnected-(U2-PB9-Pad46)") (class "Default")
      (node (ref "U2") (pin "46") (pinfunction "PB9_46") (pintype "bidirectional"))
    )
    (net (code "103") (name "unconnected-(U2-PB10-Pad21)") (class "Default")
      (node (ref "U2") (pin "21") (pinfunction "PB10_21") (pintype "bidirectional"))
    )
    (net (code "104") (name "unconnected-(U2-PB11-Pad22)") (class "Default")
      (node (ref "U2") (pin "22") (pinfunction "PB11_22") (pintype "bidirectional"))
    )
    (net (code "105") (name "unconnected-(U2-PB12-Pad25)") (class "Default")
      (node (ref "U2") (pin "25") (pinfunction "PB12_25") (pintype "bidirectional"))
    )
    (net (code "106") (name "unconnected-(U2-PB13-Pad26)") (class "Default")
      (node (ref "U2") (pin "26") (pinfunction "PB13_26") (pintype "bidirectional"))
    )
    (net (code "107") (name "unconnected-(U2-PB14-Pad27)") (class "Default")
      (node (ref "U2") (pin "27") (pinfunction "PB14_27") (pintype "bidirectional"))
    )
    (net (code "108") (name "unconnected-(U2-PB15-Pad28)") (class "Default")
      (node (ref "U2") (pin "28") (pinfunction "PB15_28") (pintype "bidirectional"))
    )
    (net (code "109") (name "unconnected-(U2-PC14-OSC32_IN-Pad3)") (class "Default")
      (node (ref "U2") (pin "3") (pinfunction "PC14-OSC32_IN_3") (pintype "bidirectional"))
    )
    (net (code "110") (name "unconnected-(U2-PC15-OSC32_OUT-Pad4)") (class "Default")
      (node (ref "U2") (pin "4") (pinfunction "PC15-OSC32_OUT_4") (pintype "bidirectional"))
    )
    (net (code "111") (name "unconnected-(U2-VBAT-Pad1)") (class "Default")
      (node (ref "U2") (pin "1") (pinfunction "VBAT_1") (pintype "bidirectional"))
    )
    (net (code "112") (name "unconnected-(U3-GND-Pad8)") (class "Default")
      (node (ref "U3") (pin "8") (pinfunction "GND_8") (pintype "passive"))
    )
    (net (code "113") (name "unconnected-(U3-PRENSENCE-Pad4)") (class "Default")
      (node (ref "U3") (pin "4") (pinfunction "PRENSENCE_4") (pintype "passive"))
    )
    (net (code "114") (name "unconnected-(U3-VPP-Pad6)") (class "Default")
      (node (ref "U3") (pin "6") (pinfunction "VPP_6") (pintype "passive"))
    )
  )
)
